# SCH_arduino_uno_cong.net
KiCad netlist of a schematic drawn in Altium Designer
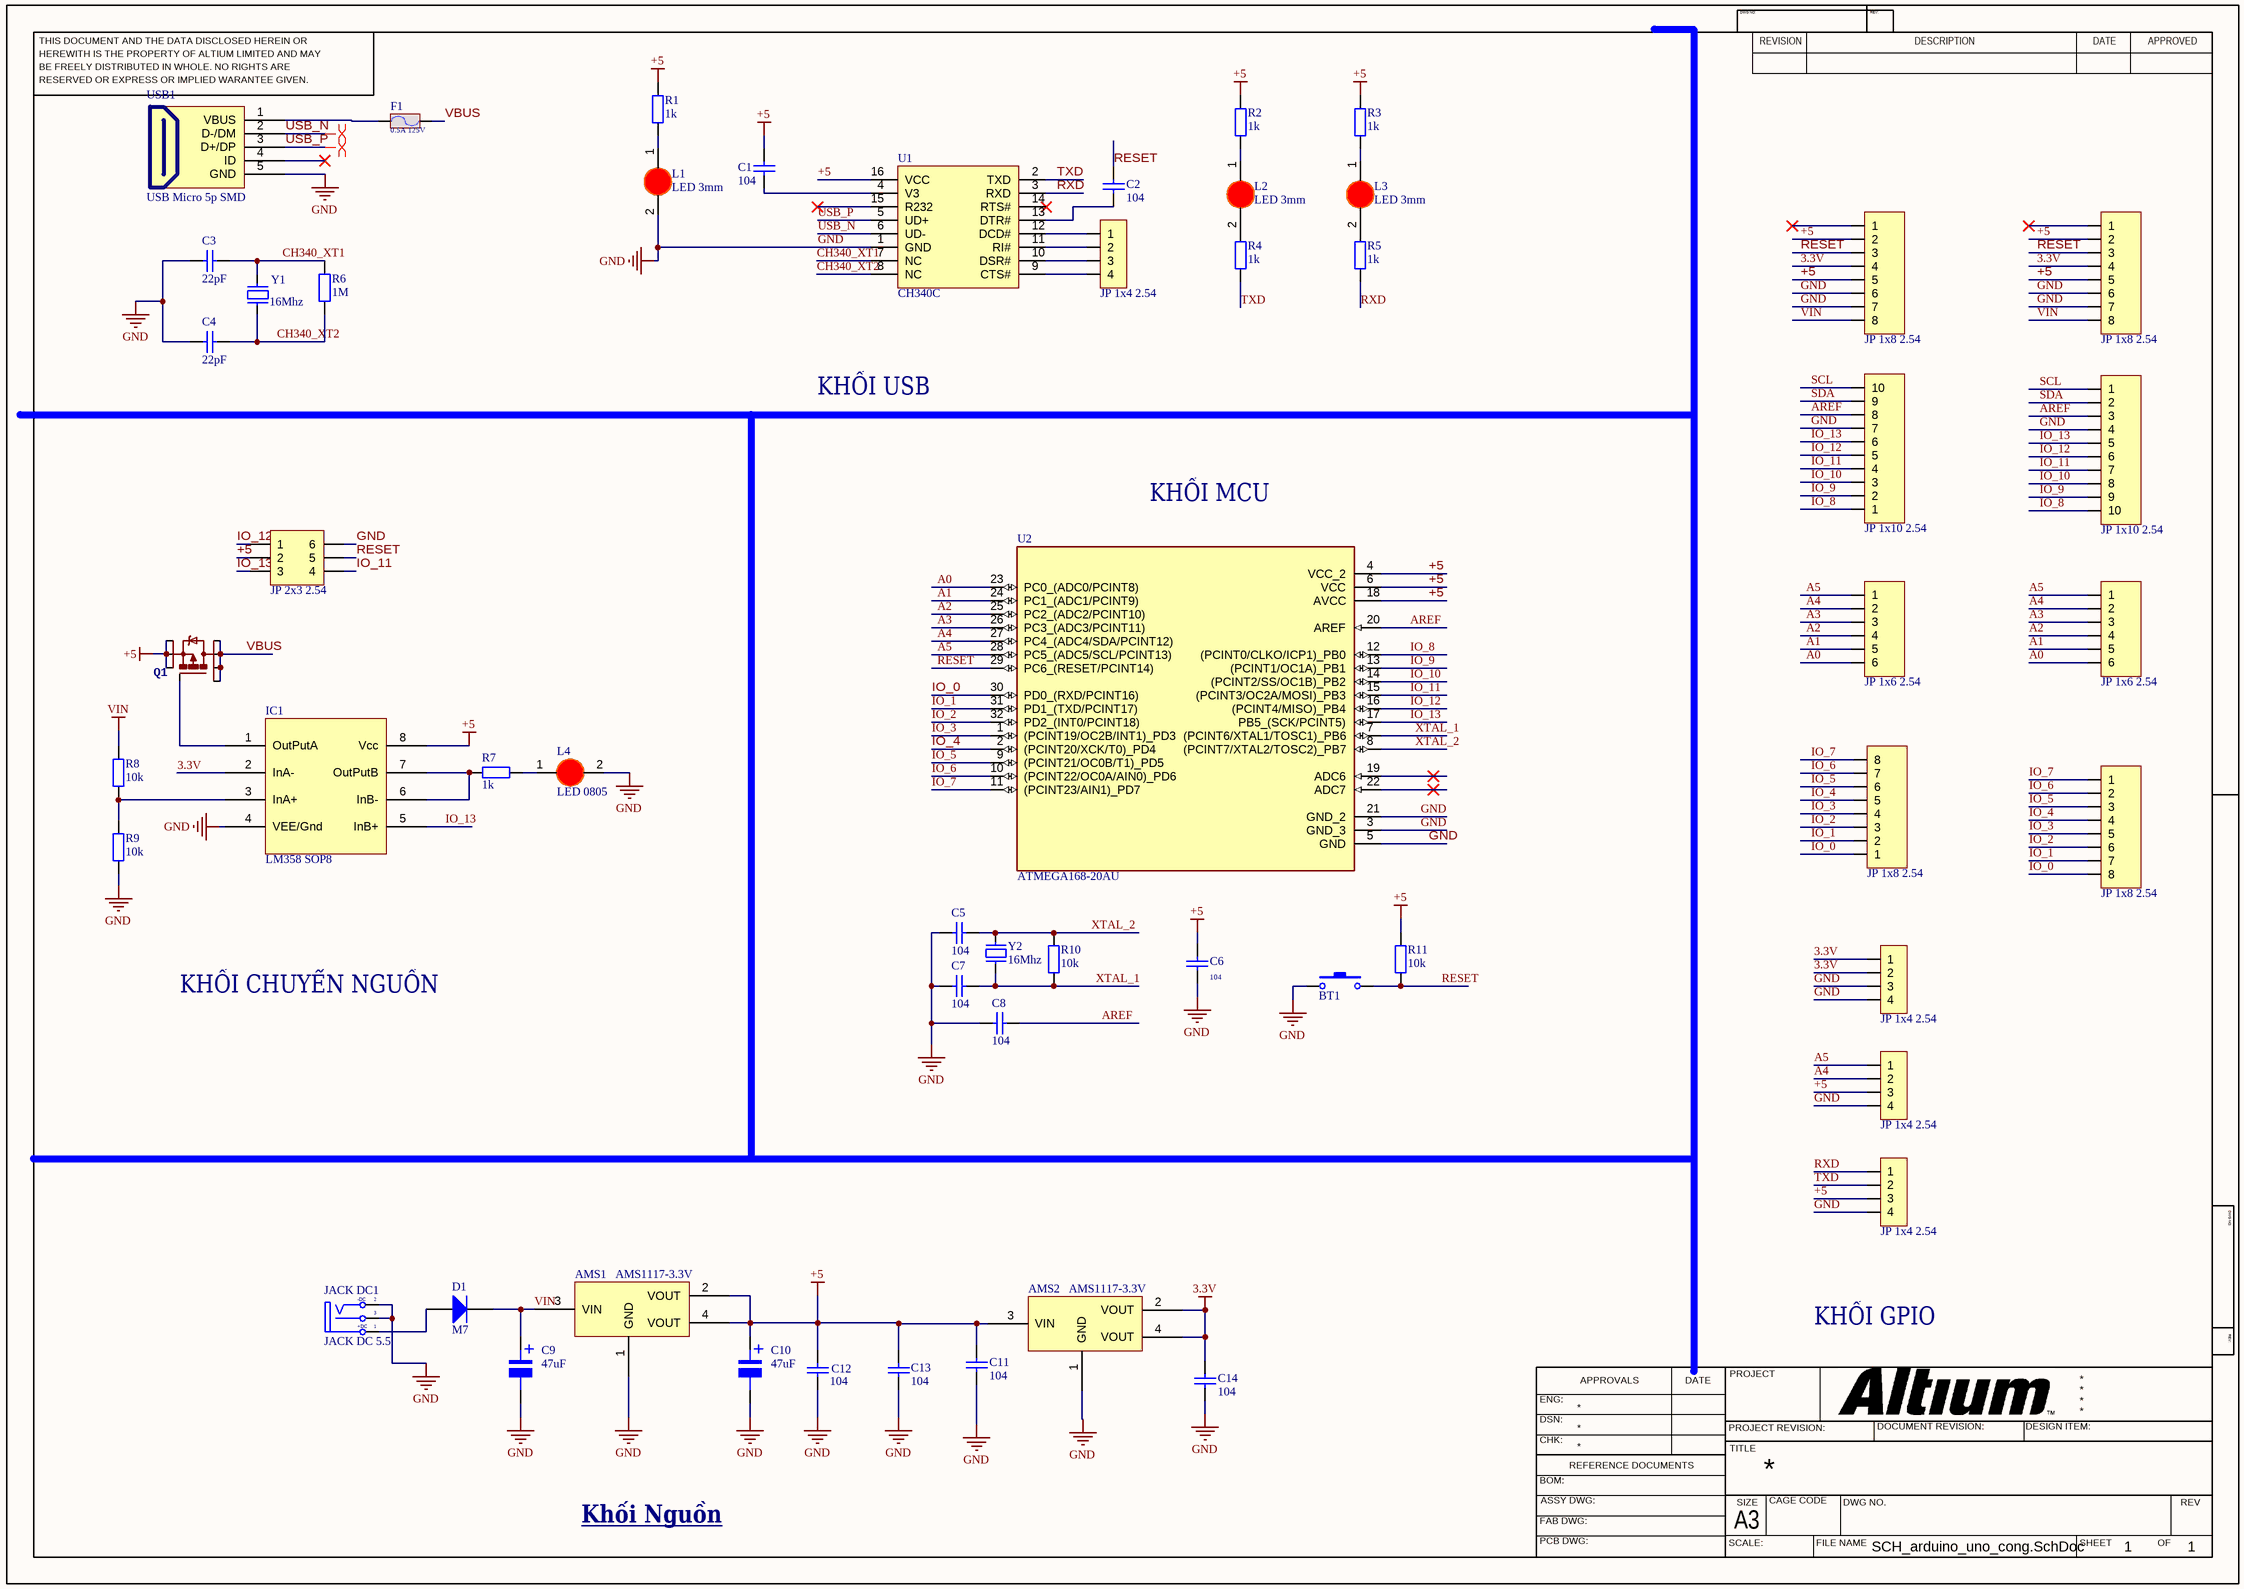
[diagram p0: SCH_arduino_uno_cong.SchDoc]

(export (version "E")
  (design (tool "Eeschema 10.0.6"))
  (components
    (comp (ref "AMS1")
      (value "AMS1117-3.3V")
      (footprint "SOT223")
      (description "Dán")
      (libsource (lib "Altium_Lib_by_KhueNguyenCreator") (part "AMS1117 SMD"))
    )
    (comp (ref "AMS2")
      (value "AMS1117-3.3V")
      (footprint "SOT223")
      (description "Dán")
      (libsource (lib "Altium_Lib_by_KhueNguyenCreator") (part "AMS1117 SMD"))
    )
    (comp (ref "BT1")
      (value "Nut Nhan 2 Chan SMD 3x6x2.5")
      (footprint "Nut Nhan 2 Chan SMD 3x6x2.5")
      (libsource (lib "Altium_Lib_by_KhueNguyenCreator") (part "Nut Nhan 2 Chan SMD 3x6x2.5"))
    )
    (comp (ref "C1")
      (value "104")
      (footprint "tu 0805")
      (description "Dán")
      (libsource (lib "Altium_Lib_by_KhueNguyenCreator") (part "Tu 0805 104 50V 10%"))
    )
    (comp (ref "C2")
      (value "104")
      (footprint "tu 0805")
      (description "Dán")
      (libsource (lib "Altium_Lib_by_KhueNguyenCreator") (part "Tu 0805 104 50V 10%"))
    )
    (comp (ref "C3")
      (value "22pF")
      (footprint "tu 0805")
      (description "Dán")
      (libsource (lib "Altium_Lib_by_KhueNguyenCreator") (part "Tu 0805 22pF 50V 10%"))
    )
    (comp (ref "C4")
      (value "22pF")
      (footprint "tu 0805")
      (description "Dán")
      (libsource (lib "Altium_Lib_by_KhueNguyenCreator") (part "Tu 0805 22pF 50V 10%"))
    )
    (comp (ref "C5")
      (value "104")
      (footprint "tu 0805")
      (description "Dán")
      (libsource (lib "Altium_Lib_by_KhueNguyenCreator") (part "Tu 0805 104 50V 10%"))
    )
    (comp (ref "C6")
      (value "104")
      (footprint "tu 0805")
      (description "Dán")
      (libsource (lib "Altium_Lib_by_KhueNguyenCreator") (part "Tu 0805 104 50V 10%"))
    )
    (comp (ref "C7")
      (value "104")
      (footprint "tu 0805")
      (description "Dán")
      (libsource (lib "Altium_Lib_by_KhueNguyenCreator") (part "Tu 0805 104 50V 10%"))
    )
    (comp (ref "C8")
      (value "104")
      (footprint "tu 0805")
      (description "Dán")
      (libsource (lib "Altium_Lib_by_KhueNguyenCreator") (part "Tu 0805 104 50V 10%"))
    )
    (comp (ref "C9")
      (value "47uF")
      (footprint "tu nhom 6.3 (d)")
      (description "Dán")
      (libsource (lib "Altium_Lib_by_KhueNguyenCreator") (part "Tu Nhom 47uF 25V"))
    )
    (comp (ref "C10")
      (value "47uF")
      (footprint "tu nhom 6.3 (d)")
      (description "Dán")
      (libsource (lib "Altium_Lib_by_KhueNguyenCreator") (part "Tu Nhom 47uF 25V"))
    )
    (comp (ref "C11")
      (value "104")
      (footprint "tu 0805")
      (description "Dán")
      (libsource (lib "Altium_Lib_by_KhueNguyenCreator") (part "Tu 0805 104 50V 10%"))
    )
    (comp (ref "C12")
      (value "104")
      (footprint "tu 0805")
      (description "Dán")
      (libsource (lib "Altium_Lib_by_KhueNguyenCreator") (part "Tu 0805 104 50V 10%"))
    )
    (comp (ref "C13")
      (value "104")
      (footprint "tu 0805")
      (description "Dán")
      (libsource (lib "Altium_Lib_by_KhueNguyenCreator") (part "Tu 0805 104 50V 10%"))
    )
    (comp (ref "C14")
      (value "104")
      (footprint "tu 0805")
      (description "Dán")
      (libsource (lib "Altium_Lib_by_KhueNguyenCreator") (part "Tu 0805 104 50V 10%"))
    )
    (comp (ref "D1")
      (value "M7")
      (footprint "DIODE SMA")
      (description "Dán")
      (libsource (lib "Altium_Lib_by_KhueNguyenCreator") (part "Diode M7 ( 4007 )"))
    )
    (comp (ref "F1")
      (value "0.5A 125V")
      (footprint "Cau Chi SMD1808")
      (description "Cau chi 0.5A 125V SMD1808")
      (libsource (lib "Altium_Lib_by_KhueNguyenCreator") (part "Cau chi 0.5A 125V SMD1808"))
    )
    (comp (ref "IC1")
      (value "LM358 SOP8")
      (footprint "SOP 8")
      (description "Dán")
      (libsource (lib "Altium_Lib_by_KhueNguyenCreator") (part "LM358 SOP8"))
    )
    (comp (ref "JACK DC1")
      (value "JACK DC 5.5")
      (footprint "JACK DC 5.5")
      (libsource (lib "Altium_Lib_by_KhueNguyenCreator") (part "JACK DC 5.5"))
    )
    (comp (ref "JP1")
      (value "JP 1x8 2.54")
      (footprint "JP 1x8 CT")
      (description "Cắm")
      (libsource (lib "Altium_Lib_by_KhueNguyenCreator") (part "JP 1x8 2.54 Cai Thang"))
    )
    (comp (ref "JP2")
      (value "JP 1x8 2.54")
      (footprint "JP 1x8 DT")
      (description "Cắm")
      (libsource (lib "Altium_Lib_by_KhueNguyenCreator") (part "JP 1x8 2.54 Duc Thang"))
    )
    (comp (ref "JP3")
      (value "JP 1x4 2.54")
      (footprint "JP 1x4 CT")
      (description "Cắm")
      (libsource (lib "Altium_Lib_by_KhueNguyenCreator") (part "JP 1x4 2.54 Cai Thang"))
    )
    (comp (ref "JP4")
      (value "JP 1x10 2.54")
      (footprint "JP 1x10 CT")
      (description "Cắm")
      (libsource (lib "Altium_Lib_by_KhueNguyenCreator") (part "JP 1x10 2.54 Cai Thang"))
    )
    (comp (ref "JP5")
      (value "JP 1x10 2.54")
      (footprint "JP 1x10 DT")
      (description "Cắm")
      (libsource (lib "Altium_Lib_by_KhueNguyenCreator") (part "JP 1x10 2.54 Duc Thang"))
    )
    (comp (ref "JP6")
      (value "JP 2x3 2.54")
      (footprint "JP 2x3 DT")
      (description "Cắm")
      (libsource (lib "Altium_Lib_by_KhueNguyenCreator") (part "JP 2x3 2.54 Duc Thang"))
    )
    (comp (ref "JP7")
      (value "JP 1x6 2.54")
      (footprint "JP 1x6 CT")
      (description "Cắm")
      (libsource (lib "Altium_Lib_by_KhueNguyenCreator") (part "JP 1x6 2.54 Cai Thang"))
    )
    (comp (ref "JP8")
      (value "JP 1x6 2.54")
      (footprint "JP 1x6 DT")
      (description "Cắm")
      (libsource (lib "Altium_Lib_by_KhueNguyenCreator") (part "JP 1x6 2.54 Duc Thang"))
    )
    (comp (ref "JP9")
      (value "JP 1x8 2.54")
      (footprint "JP 1x8 CT")
      (description "Cắm")
      (libsource (lib "") (part "JP 1x8 2.54 Cai Thang_1"))
    )
    (comp (ref "JP10")
      (value "JP 1x8 2.54")
      (footprint "JP 1x8 DT")
      (description "Cắm")
      (libsource (lib "Altium_Lib_by_KhueNguyenCreator") (part "JP 1x8 2.54 Duc Thang"))
    )
    (comp (ref "JP11")
      (value "JP 1x4 2.54")
      (footprint "JP 1x4 CT")
      (description "Cắm")
      (libsource (lib "Altium_Lib_by_KhueNguyenCreator") (part "JP 1x4 2.54 Cai Thang"))
    )
    (comp (ref "JP12")
      (value "JP 1x4 2.54")
      (footprint "JP 1x4 CT")
      (description "Cắm")
      (libsource (lib "Altium_Lib_by_KhueNguyenCreator") (part "JP 1x4 2.54 Cai Thang"))
    )
    (comp (ref "JP13")
      (value "JP 1x4 2.54")
      (footprint "JP 1x4 CT")
      (description "Cắm")
      (libsource (lib "Altium_Lib_by_KhueNguyenCreator") (part "JP 1x4 2.54 Cai Thang"))
    )
    (comp (ref "L1")
      (value "LED 3mm")
      (footprint "LED-3MM-RED")
      (description "Cắm")
      (libsource (lib "Altium_Lib_by_KhueNguyenCreator") (part "LED 3mm Do"))
    )
    (comp (ref "L2")
      (value "LED 3mm")
      (footprint "LED-3MM-RED")
      (description "Cắm")
      (libsource (lib "Altium_Lib_by_KhueNguyenCreator") (part "LED 3mm Do"))
    )
    (comp (ref "L3")
      (value "LED 3mm")
      (footprint "LED-3MM-RED")
      (description "Cắm")
      (libsource (lib "Altium_Lib_by_KhueNguyenCreator") (part "LED 3mm Do"))
    )
    (comp (ref "L4")
      (value "LED 0805")
      (footprint "LED-0805-Red")
      (description "Dán")
      (libsource (lib "Altium_Lib_by_KhueNguyenCreator") (part "LED 0805 Do"))
    )
    (comp (ref "Q1")
      (value "MOSFET_P")
      (footprint "SO-8")
      (description "MOSFET P-CH 30V 5.8A 8-SOIC")
      (fields (field (name "PART NUMBER") "Q000008") (field (name "MANUFACTURER PART NUMBER") "IRF7406TRPBF"))
      (libsource (lib "open-components") (part "MOSFET_P"))
    )
    (comp (ref "R1")
      (value "1k")
      (footprint "tro smd 0805")
      (description "Dán")
      (libsource (lib "Altium_Lib_by_KhueNguyenCreator") (part "Tro 0805 1% 1k"))
    )
    (comp (ref "R2")
      (value "1k")
      (footprint "tro smd 0805")
      (description "Dán")
      (libsource (lib "Altium_Lib_by_KhueNguyenCreator") (part "Tro 0805 1% 1k"))
    )
    (comp (ref "R3")
      (value "1k")
      (footprint "tro smd 0805")
      (description "Dán")
      (libsource (lib "Altium_Lib_by_KhueNguyenCreator") (part "Tro 0805 1% 1k"))
    )
    (comp (ref "R4")
      (value "1k")
      (footprint "tro smd 0805")
      (description "Dán")
      (libsource (lib "Altium_Lib_by_KhueNguyenCreator") (part "Tro 0805 1% 1k"))
    )
    (comp (ref "R5")
      (value "1k")
      (footprint "tro smd 0805")
      (description "Dán")
      (libsource (lib "Altium_Lib_by_KhueNguyenCreator") (part "Tro 0805 1% 1k"))
    )
    (comp (ref "R6")
      (value "1M")
      (footprint "tro smd 0805")
      (description "Dán")
      (libsource (lib "Altium_Lib_by_KhueNguyenCreator") (part "Tro 0805 5% 1M"))
    )
    (comp (ref "R7")
      (value "1k")
      (footprint "tro smd 0805")
      (description "Dán")
      (libsource (lib "Altium_Lib_by_KhueNguyenCreator") (part "Tro 0805 5% 1k"))
    )
    (comp (ref "R8")
      (value "10k")
      (footprint "tro smd 0805")
      (description "Dán")
      (libsource (lib "Altium_Lib_by_KhueNguyenCreator") (part "Tro 0805 1% 10k"))
    )
    (comp (ref "R9")
      (value "10k")
      (footprint "tro smd 0805")
      (description "Dán")
      (libsource (lib "Altium_Lib_by_KhueNguyenCreator") (part "Tro 0805 1% 10k"))
    )
    (comp (ref "R10")
      (value "10k")
      (footprint "tro smd 0805")
      (description "Dán")
      (libsource (lib "Altium_Lib_by_KhueNguyenCreator") (part "Tro 0805 1% 10k"))
    )
    (comp (ref "R11")
      (value "10k")
      (footprint "tro smd 0805")
      (description "Dán")
      (libsource (lib "Altium_Lib_by_KhueNguyenCreator") (part "Tro 0805 5% 10k"))
    )
    (comp (ref "U1")
      (value "CH340C")
      (footprint "SOIC16_50_284_25X90_SMT")
      (description "USB Bridge, USB to UART USB 2.0 UART Interface")
      (fields (field (name "MANUFACTURER") "Olimex"))
      (libsource (lib "Altium_Lib_by_KhueNguyenCreator") (part "CH340C"))
    )
    (comp (ref "U2")
      (value "ATMEGA168-20AU")
      (footprint "ATMEGA168")
      (description "AVR AVRÂ® ATmega Microcontroller IC 8-Bit 20MHz 16KB _8K x 16_ FLASH 32-TQFP _7x7_")
      (fields (field (name "MF") "Microchip"))
      (libsource (lib "Altium_Lib_by_KhueNguyenCreator") (part "ATMEGA168-20AU"))
    )
    (comp (ref "USB1")
      (value "USB Micro 5p SMD")
      (footprint "USB Micro 5p SMD")
      (description "USB Type B")
      (libsource (lib "Altium_Lib_by_KhueNguyenCreator") (part "USB Micro 5p SMD"))
    )
    (comp (ref "Y1")
      (value "16Mhz")
      (footprint "Thach Anh 2 chan SMD")
      (description "Crystal For all Crystal 2pin.")
      (libsource (lib "Altium_Lib_by_KhueNguyenCreator") (part "Thach Anh 2 chan SMD"))
    )
    (comp (ref "Y2")
      (value "16Mhz")
      (footprint "Thach Anh 2 chan SMD")
      (description "Crystal For all Crystal 2pin.")
      (libsource (lib "Altium_Lib_by_KhueNguyenCreator") (part "Thach Anh 2 chan SMD"))
    )
  )
  (nets
    (net (code "1") (name "+5") (class "Default")
      (node (ref "AMS1") (pin "2") (pinfunction "VOUT_2") (pintype "passive"))
      (node (ref "AMS1") (pin "4") (pinfunction "VOUT_4") (pintype "passive"))
      (node (ref "AMS2") (pin "3") (pinfunction "VIN_3") (pintype "passive"))
      (node (ref "C1") (pin "1") (pinfunction "1_1") (pintype "passive"))
      (node (ref "C10") (pin "1") (pinfunction "1_1") (pintype "passive"))
      (node (ref "C11") (pin "2") (pinfunction "2_2") (pintype "passive"))
      (node (ref "C12") (pin "2") (pinfunction "2_2") (pintype "passive"))
      (node (ref "C13") (pin "2") (pinfunction "2_2") (pintype "passive"))
      (node (ref "C6") (pin "1") (pinfunction "1_1") (pintype "passive"))
      (node (ref "IC1") (pin "8") (pinfunction "Vcc_8") (pintype "passive"))
      (node (ref "JP1") (pin "2") (pinfunction "2_2") (pintype "passive"))
      (node (ref "JP1") (pin "5") (pinfunction "5_5") (pintype "passive"))
      (node (ref "JP12") (pin "3") (pinfunction "3_3") (pintype "passive"))
      (node (ref "JP13") (pin "3") (pinfunction "3_3") (pintype "passive"))
      (node (ref "JP2") (pin "2") (pinfunction "2_2") (pintype "passive"))
      (node (ref "JP2") (pin "5") (pinfunction "5_5") (pintype "passive"))
      (node (ref "JP6") (pin "2") (pinfunction "2_2") (pintype "passive"))
      (node (ref "Q1") (pin "1") (pinfunction "S_1") (pintype "passive"))
      (node (ref "Q1") (pin "2") (pinfunction "S_2") (pintype "passive"))
      (node (ref "Q1") (pin "3") (pinfunction "S_3") (pintype "passive"))
      (node (ref "R1") (pin "2") (pinfunction "2_2") (pintype "passive"))
      (node (ref "R11") (pin "2") (pinfunction "2_2") (pintype "passive"))
      (node (ref "R2") (pin "2") (pinfunction "2_2") (pintype "passive"))
      (node (ref "R3") (pin "2") (pinfunction "2_2") (pintype "passive"))
      (node (ref "U1") (pin "16") (pinfunction "VCC_16") (pintype "passive"))
      (node (ref "U2") (pin "18") (pinfunction "AVCC_18") (pintype "power_in"))
      (node (ref "U2") (pin "4") (pinfunction "VCC_2_4") (pintype "power_in"))
      (node (ref "U2") (pin "6") (pinfunction "VCC_6") (pintype "power_in"))
    )
    (net (code "2") (name "/A0") (class "Default")
      (node (ref "JP7") (pin "6") (pinfunction "6_6") (pintype "passive"))
      (node (ref "JP8") (pin "6") (pinfunction "6_6") (pintype "passive"))
      (node (ref "U2") (pin "23") (pinfunction "PC0_(ADC0/PCINT8)_23") (pintype "bidirectional"))
    )
    (net (code "3") (name "/A1") (class "Default")
      (node (ref "JP7") (pin "5") (pinfunction "5_5") (pintype "passive"))
      (node (ref "JP8") (pin "5") (pinfunction "5_5") (pintype "passive"))
      (node (ref "U2") (pin "24") (pinfunction "PC1_(ADC1/PCINT9)_24") (pintype "bidirectional"))
    )
    (net (code "4") (name "/A2") (class "Default")
      (node (ref "JP7") (pin "4") (pinfunction "4_4") (pintype "passive"))
      (node (ref "JP8") (pin "4") (pinfunction "4_4") (pintype "passive"))
      (node (ref "U2") (pin "25") (pinfunction "PC2_(ADC2/PCINT10)_25") (pintype "bidirectional"))
    )
    (net (code "5") (name "/A3") (class "Default")
      (node (ref "JP7") (pin "3") (pinfunction "3_3") (pintype "passive"))
      (node (ref "JP8") (pin "3") (pinfunction "3_3") (pintype "passive"))
      (node (ref "U2") (pin "26") (pinfunction "PC3_(ADC3/PCINT11)_26") (pintype "bidirectional"))
    )
    (net (code "6") (name "/A4") (class "Default")
      (node (ref "JP12") (pin "2") (pinfunction "2_2") (pintype "passive"))
      (node (ref "JP7") (pin "2") (pinfunction "2_2") (pintype "passive"))
      (node (ref "JP8") (pin "2") (pinfunction "2_2") (pintype "passive"))
      (node (ref "U2") (pin "27") (pinfunction "PC4_(ADC4/SDA/PCINT12)_27") (pintype "bidirectional"))
    )
    (net (code "7") (name "/A5") (class "Default")
      (node (ref "JP12") (pin "1") (pinfunction "1_1") (pintype "passive"))
      (node (ref "JP7") (pin "1") (pinfunction "1_1") (pintype "passive"))
      (node (ref "JP8") (pin "1") (pinfunction "1_1") (pintype "passive"))
      (node (ref "U2") (pin "28") (pinfunction "PC5_(ADC5/SCL/PCINT13)_28") (pintype "bidirectional"))
    )
    (net (code "8") (name "/AREF") (class "Default")
      (node (ref "C8") (pin "1") (pinfunction "1_1") (pintype "passive"))
      (node (ref "JP4") (pin "8") (pinfunction "8_8") (pintype "passive"))
      (node (ref "JP5") (pin "3") (pinfunction "3_3") (pintype "passive"))
      (node (ref "U2") (pin "20") (pinfunction "AREF_20") (pintype "input"))
    )
    (net (code "9") (name "/CH340_XT1") (class "Default")
      (node (ref "C3") (pin "1") (pinfunction "1_1") (pintype "passive"))
      (node (ref "R6") (pin "2") (pinfunction "2_2") (pintype "passive"))
      (node (ref "U1") (pin "7") (pinfunction "NC_7") (pintype "passive"))
      (node (ref "Y1") (pin "2") (pinfunction "2_2") (pintype "passive"))
    )
    (net (code "10") (name "/CH340_XT2") (class "Default")
      (node (ref "C4") (pin "1") (pinfunction "1_1") (pintype "passive"))
      (node (ref "R6") (pin "1") (pinfunction "1_1") (pintype "passive"))
      (node (ref "U1") (pin "8") (pinfunction "NC_8") (pintype "passive"))
      (node (ref "Y1") (pin "1") (pinfunction "1_1") (pintype "passive"))
    )
    (net (code "11") (name "/IO_0") (class "Default")
      (node (ref "JP10") (pin "8") (pinfunction "8_8") (pintype "passive"))
      (node (ref "JP9") (pin "1") (pinfunction "1_1") (pintype "passive"))
      (node (ref "U2") (pin "30") (pinfunction "PD0_(RXD/PCINT16)_30") (pintype "bidirectional"))
    )
    (net (code "12") (name "/IO_1") (class "Default")
      (node (ref "JP10") (pin "7") (pinfunction "7_7") (pintype "passive"))
      (node (ref "JP9") (pin "2") (pinfunction "2_2") (pintype "passive"))
      (node (ref "U2") (pin "31") (pinfunction "PD1_(TXD/PCINT17)_31") (pintype "bidirectional"))
    )
    (net (code "13") (name "/IO_2") (class "Default")
      (node (ref "JP10") (pin "6") (pinfunction "6_6") (pintype "passive"))
      (node (ref "JP9") (pin "3") (pinfunction "3_3") (pintype "passive"))
      (node (ref "U2") (pin "32") (pinfunction "PD2_(INT0/PCINT18)_32") (pintype "bidirectional"))
    )
    (net (code "14") (name "/IO_3") (class "Default")
      (node (ref "JP10") (pin "5") (pinfunction "5_5") (pintype "passive"))
      (node (ref "JP9") (pin "4") (pinfunction "4_4") (pintype "passive"))
      (node (ref "U2") (pin "1") (pinfunction "(PCINT19/OC2B/INT1)_PD3_1") (pintype "bidirectional"))
    )
    (net (code "15") (name "/IO_4") (class "Default")
      (node (ref "JP10") (pin "4") (pinfunction "4_4") (pintype "passive"))
      (node (ref "JP9") (pin "5") (pinfunction "5_5") (pintype "passive"))
      (node (ref "U2") (pin "2") (pinfunction "(PCINT20/XCK/T0)_PD4_2") (pintype "bidirectional"))
    )
    (net (code "16") (name "/IO_5") (class "Default")
      (node (ref "JP10") (pin "3") (pinfunction "3_3") (pintype "passive"))
      (node (ref "JP9") (pin "6") (pinfunction "6_6") (pintype "passive"))
      (node (ref "U2") (pin "9") (pinfunction "(PCINT21/OC0B/T1)_PD5_9") (pintype "bidirectional"))
    )
    (net (code "17") (name "/IO_6") (class "Default")
      (node (ref "JP10") (pin "2") (pinfunction "2_2") (pintype "passive"))
      (node (ref "JP9") (pin "7") (pinfunction "7_7") (pintype "passive"))
      (node (ref "U2") (pin "10") (pinfunction "(PCINT22/OC0A/AIN0)_PD6_10") (pintype "bidirectional"))
    )
    (net (code "18") (name "/IO_7") (class "Default")
      (node (ref "JP10") (pin "1") (pinfunction "1_1") (pintype "passive"))
      (node (ref "JP9") (pin "8") (pinfunction "8_8") (pintype "passive"))
      (node (ref "U2") (pin "11") (pinfunction "(PCINT23/AIN1)_PD7_11") (pintype "bidirectional"))
    )
    (net (code "19") (name "/IO_8") (class "Default")
      (node (ref "JP4") (pin "1") (pinfunction "1_1") (pintype "passive"))
      (node (ref "JP5") (pin "10") (pinfunction "10_10") (pintype "passive"))
      (node (ref "U2") (pin "12") (pinfunction "(PCINT0/CLKO/ICP1)_PB0_12") (pintype "bidirectional"))
    )
    (net (code "20") (name "/IO_9") (class "Default")
      (node (ref "JP4") (pin "2") (pinfunction "2_2") (pintype "passive"))
      (node (ref "JP5") (pin "9") (pinfunction "9_9") (pintype "passive"))
      (node (ref "U2") (pin "13") (pinfunction "(PCINT1/OC1A)_PB1_13") (pintype "bidirectional"))
    )
    (net (code "21") (name "/IO_10") (class "Default")
      (node (ref "JP4") (pin "3") (pinfunction "3_3") (pintype "passive"))
      (node (ref "JP5") (pin "8") (pinfunction "8_8") (pintype "passive"))
      (node (ref "U2") (pin "14") (pinfunction "(PCINT2/SS/OC1B)_PB2_14") (pintype "bidirectional"))
    )
    (net (code "22") (name "/IO_11") (class "Default")
      (node (ref "JP4") (pin "4") (pinfunction "4_4") (pintype "passive"))
      (node (ref "JP5") (pin "7") (pinfunction "7_7") (pintype "passive"))
      (node (ref "JP6") (pin "4") (pinfunction "4_4") (pintype "passive"))
      (node (ref "U2") (pin "15") (pinfunction "(PCINT3/OC2A/MOSI)_PB3_15") (pintype "bidirectional"))
    )
    (net (code "23") (name "/IO_12") (class "Default")
      (node (ref "JP4") (pin "5") (pinfunction "5_5") (pintype "passive"))
      (node (ref "JP5") (pin "6") (pinfunction "6_6") (pintype "passive"))
      (node (ref "JP6") (pin "1") (pinfunction "1_1") (pintype "passive"))
      (node (ref "U2") (pin "16") (pinfunction "(PCINT4/MISO)_PB4_16") (pintype "bidirectional"))
    )
    (net (code "24") (name "/IO_13") (class "Default")
      (node (ref "IC1") (pin "5") (pinfunction "InB+_5") (pintype "passive"))
      (node (ref "JP4") (pin "6") (pinfunction "6_6") (pintype "passive"))
      (node (ref "JP5") (pin "5") (pinfunction "5_5") (pintype "passive"))
      (node (ref "JP6") (pin "3") (pinfunction "3_3") (pintype "passive"))
      (node (ref "U2") (pin "17") (pinfunction "PB5_(SCK/PCINT5)_17") (pintype "bidirectional"))
    )
    (net (code "25") (name "/RESET") (class "Default")
      (node (ref "BT1") (pin "2") (pinfunction "2_2") (pintype "passive"))
      (node (ref "C2") (pin "1") (pinfunction "1_1") (pintype "passive"))
      (node (ref "JP1") (pin "3") (pinfunction "3_3") (pintype "passive"))
      (node (ref "JP2") (pin "3") (pinfunction "3_3") (pintype "passive"))
      (node (ref "JP6") (pin "5") (pinfunction "5_5") (pintype "passive"))
      (node (ref "R11") (pin "1") (pinfunction "1_1") (pintype "passive"))
      (node (ref "U2") (pin "29") (pinfunction "PC6_(RESET/PCINT14)_29") (pintype "bidirectional"))
    )
    (net (code "26") (name "/RXD") (class "Default")
      (node (ref "JP13") (pin "1") (pinfunction "1_1") (pintype "passive"))
      (node (ref "R5") (pin "1") (pinfunction "1_1") (pintype "passive"))
      (node (ref "U1") (pin "3") (pinfunction "RXD_3") (pintype "passive"))
    )
    (net (code "27") (name "/SCL") (class "Default")
      (node (ref "JP4") (pin "10") (pinfunction "10_10") (pintype "passive"))
      (node (ref "JP5") (pin "1") (pinfunction "1_1") (pintype "passive"))
    )
    (net (code "28") (name "/SDA") (class "Default")
      (node (ref "JP4") (pin "9") (pinfunction "9_9") (pintype "passive"))
      (node (ref "JP5") (pin "2") (pinfunction "2_2") (pintype "passive"))
    )
    (net (code "29") (name "/TXD") (class "Default")
      (node (ref "JP13") (pin "2") (pinfunction "2_2") (pintype "passive"))
      (node (ref "R4") (pin "1") (pinfunction "1_1") (pintype "passive"))
      (node (ref "U1") (pin "2") (pinfunction "TXD_2") (pintype "passive"))
    )
    (net (code "30") (name "/USB_N") (class "Default")
      (node (ref "U1") (pin "6") (pinfunction "UD-_6") (pintype "passive"))
      (node (ref "USB1") (pin "2") (pinfunction "D-/DM_2") (pintype "passive"))
    )
    (net (code "31") (name "/USB_P") (class "Default")
      (node (ref "U1") (pin "5") (pinfunction "UD+_5") (pintype "passive"))
      (node (ref "USB1") (pin "3") (pinfunction "D+/DP_3") (pintype "passive"))
    )
    (net (code "32") (name "/VBUS") (class "Default")
      (node (ref "F1") (pin "2") (pinfunction "2_2") (pintype "passive"))
      (node (ref "Q1") (pin "5") (pinfunction "D_5") (pintype "passive"))
      (node (ref "Q1") (pin "6") (pinfunction "D_6") (pintype "passive"))
      (node (ref "Q1") (pin "7") (pinfunction "D_7") (pintype "passive"))
      (node (ref "Q1") (pin "8") (pinfunction "D_8") (pintype "passive"))
    )
    (net (code "33") (name "/XTAL_1") (class "Default")
      (node (ref "C7") (pin "1") (pinfunction "1_1") (pintype "passive"))
      (node (ref "R10") (pin "1") (pinfunction "1_1") (pintype "passive"))
      (node (ref "U2") (pin "7") (pinfunction "(PCINT6/XTAL1/TOSC1)_PB6_7") (pintype "bidirectional"))
      (node (ref "Y2") (pin "1") (pinfunction "1_1") (pintype "passive"))
    )
    (net (code "34") (name "/XTAL_2") (class "Default")
      (node (ref "C5") (pin "1") (pinfunction "1_1") (pintype "passive"))
      (node (ref "R10") (pin "2") (pinfunction "2_2") (pintype "passive"))
      (node (ref "U2") (pin "8") (pinfunction "(PCINT7/XTAL2/TOSC2)_PB7_8") (pintype "bidirectional"))
      (node (ref "Y2") (pin "2") (pinfunction "2_2") (pintype "passive"))
    )
    (net (code "35") (name "3.3V") (class "Default")
      (node (ref "AMS2") (pin "2") (pinfunction "VOUT_2") (pintype "passive"))
      (node (ref "AMS2") (pin "4") (pinfunction "VOUT_4") (pintype "passive"))
      (node (ref "C14") (pin "2") (pinfunction "2_2") (pintype "passive"))
      (node (ref "IC1") (pin "2") (pinfunction "InA-_2") (pintype "passive"))
      (node (ref "JP1") (pin "4") (pinfunction "4_4") (pintype "passive"))
      (node (ref "JP11") (pin "1") (pinfunction "1_1") (pintype "passive"))
      (node (ref "JP11") (pin "2") (pinfunction "2_2") (pintype "passive"))
      (node (ref "JP2") (pin "4") (pinfunction "4_4") (pintype "passive"))
    )
    (net (code "36") (name "GND") (class "Default")
      (node (ref "AMS1") (pin "1") (pinfunction "GND_1") (pintype "passive"))
      (node (ref "AMS2") (pin "1") (pinfunction "GND_1") (pintype "passive"))
      (node (ref "BT1") (pin "1") (pinfunction "1_1") (pintype "passive"))
      (node (ref "C10") (pin "2") (pinfunction "2_2") (pintype "passive"))
      (node (ref "C11") (pin "1") (pinfunction "1_1") (pintype "passive"))
      (node (ref "C12") (pin "1") (pinfunction "1_1") (pintype "passive"))
      (node (ref "C13") (pin "1") (pinfunction "1_1") (pintype "passive"))
      (node (ref "C14") (pin "1") (pinfunction "1_1") (pintype "passive"))
      (node (ref "C3") (pin "2") (pinfunction "2_2") (pintype "passive"))
      (node (ref "C4") (pin "2") (pinfunction "2_2") (pintype "passive"))
      (node (ref "C5") (pin "2") (pinfunction "2_2") (pintype "passive"))
      (node (ref "C6") (pin "2") (pinfunction "2_2") (pintype "passive"))
      (node (ref "C7") (pin "2") (pinfunction "2_2") (pintype "passive"))
      (node (ref "C8") (pin "2") (pinfunction "2_2") (pintype "passive"))
      (node (ref "C9") (pin "2") (pinfunction "2_2") (pintype "passive"))
      (node (ref "IC1") (pin "4") (pinfunction "VEE/Gnd_4") (pintype "passive"))
      (node (ref "JACK DC1") (pin "2") (pinfunction "TN_2") (pintype "passive"))
      (node (ref "JACK DC1") (pin "3") (pinfunction "S_3") (pintype "power_in"))
      (node (ref "JP1") (pin "6") (pinfunction "6_6") (pintype "passive"))
      (node (ref "JP1") (pin "7") (pinfunction "7_7") (pintype "passive"))
      (node (ref "JP11") (pin "3") (pinfunction "3_3") (pintype "passive"))
      (node (ref "JP11") (pin "4") (pinfunction "4_4") (pintype "passive"))
      (node (ref "JP12") (pin "4") (pinfunction "4_4") (pintype "passive"))
      (node (ref "JP13") (pin "4") (pinfunction "4_4") (pintype "passive"))
      (node (ref "JP2") (pin "6") (pinfunction "6_6") (pintype "passive"))
      (node (ref "JP2") (pin "7") (pinfunction "7_7") (pintype "passive"))
      (node (ref "JP4") (pin "7") (pinfunction "7_7") (pintype "passive"))
      (node (ref "JP5") (pin "4") (pinfunction "4_4") (pintype "passive"))
      (node (ref "JP6") (pin "6") (pinfunction "6_6") (pintype "passive"))
      (node (ref "L1") (pin "2") (pinfunction "K_2") (pintype "passive"))
      (node (ref "L4") (pin "2") (pinfunction "K_2") (pintype "passive"))
      (node (ref "R9") (pin "1") (pinfunction "1_1") (pintype "passive"))
      (node (ref "U1") (pin "1") (pinfunction "GND_1") (pintype "passive"))
      (node (ref "U2") (pin "21") (pinfunction "GND_2_21") (pintype "passive"))
      (node (ref "U2") (pin "3") (pinfunction "GND_3_3") (pintype "passive"))
      (node (ref "U2") (pin "5") (pinfunction "GND_5") (pintype "passive"))
      (node (ref "USB1") (pin "5") (pinfunction "GND_5") (pintype "passive"))
    )
    (net (code "37") (name "Net-(D1-A)") (class "Default")
      (node (ref "D1") (pin "1") (pinfunction "A_1") (pintype "passive"))
      (node (ref "JACK DC1") (pin "1") (pinfunction "T_1") (pintype "passive"))
    )
    (net (code "38") (name "Net-(IC1-InA+)") (class "Default")
      (node (ref "IC1") (pin "3") (pinfunction "InA+_3") (pintype "passive"))
      (node (ref "R8") (pin "1") (pinfunction "1_1") (pintype "passive"))
      (node (ref "R9") (pin "2") (pinfunction "2_2") (pintype "passive"))
    )
    (net (code "39") (name "Net-(IC1-InB-)") (class "Default")
      (node (ref "IC1") (pin "6") (pinfunction "InB-_6") (pintype "passive"))
      (node (ref "IC1") (pin "7") (pinfunction "OutPutB_7") (pintype "passive"))
      (node (ref "R7") (pin "1") (pinfunction "1_1") (pintype "passive"))
    )
    (net (code "40") (name "Net-(IC1-OutPutA)") (class "Default")
      (node (ref "IC1") (pin "1") (pinfunction "OutPutA_1") (pintype "passive"))
      (node (ref "Q1") (pin "4") (pinfunction "G_4") (pintype "passive"))
    )
    (net (code "41") (name "Net-(L1-A)") (class "Default")
      (node (ref "L1") (pin "1") (pinfunction "A_1") (pintype "passive"))
      (node (ref "R1") (pin "1") (pinfunction "1_1") (pintype "passive"))
    )
    (net (code "42") (name "Net-(L2-A)") (class "Default")
      (node (ref "L2") (pin "1") (pinfunction "A_1") (pintype "passive"))
      (node (ref "R2") (pin "1") (pinfunction "1_1") (pintype "passive"))
    )
    (net (code "43") (name "Net-(L2-K)") (class "Default")
      (node (ref "L2") (pin "2") (pinfunction "K_2") (pintype "passive"))
      (node (ref "R4") (pin "2") (pinfunction "2_2") (pintype "passive"))
    )
    (net (code "44") (name "Net-(L3-A)") (class "Default")
      (node (ref "L3") (pin "1") (pinfunction "A_1") (pintype "passive"))
      (node (ref "R3") (pin "1") (pinfunction "1_1") (pintype "passive"))
    )
    (net (code "45") (name "Net-(L3-K)") (class "Default")
      (node (ref "L3") (pin "2") (pinfunction "K_2") (pintype "passive"))
      (node (ref "R5") (pin "2") (pinfunction "2_2") (pintype "passive"))
    )
    (net (code "46") (name "Net-(L4-A)") (class "Default")
      (node (ref "L4") (pin "1") (pinfunction "A_1") (pintype "passive"))
      (node (ref "R7") (pin "2") (pinfunction "2_2") (pintype "passive"))
    )
    (net (code "47") (name "Net-(U1-CTS#)") (class "Default")
      (node (ref "JP3") (pin "4") (pinfunction "4_4") (pintype "passive"))
      (node (ref "U1") (pin "9") (pinfunction "CTS#_9") (pintype "passive"))
    )
    (net (code "48") (name "Net-(U1-DCD#)") (class "Default")
      (node (ref "JP3") (pin "1") (pinfunction "1_1") (pintype "passive"))
      (node (ref "U1") (pin "12") (pinfunction "DCD#_12") (pintype "passive"))
    )
    (net (code "49") (name "Net-(U1-DSR#)") (class "Default")
      (node (ref "JP3") (pin "3") (pinfunction "3_3") (pintype "passive"))
      (node (ref "U1") (pin "10") (pinfunction "DSR#_10") (pintype "passive"))
    )
    (net (code "50") (name "Net-(U1-DTR#)") (class "Default")
      (node (ref "C2") (pin "2") (pinfunction "2_2") (pintype "passive"))
      (node (ref "U1") (pin "13") (pinfunction "DTR#_13") (pintype "passive"))
    )
    (net (code "51") (name "Net-(U1-RI#)") (class "Default")
      (node (ref "JP3") (pin "2") (pinfunction "2_2") (pintype "passive"))
      (node (ref "U1") (pin "11") (pinfunction "RI#_11") (pintype "passive"))
    )
    (net (code "52") (name "Net-(U1-V3)") (class "Default")
      (node (ref "C1") (pin "2") (pinfunction "2_2") (pintype "passive"))
      (node (ref "U1") (pin "4") (pinfunction "V3_4") (pintype "passive"))
    )
    (net (code "53") (name "Net-(USB1-VBUS)") (class "Default")
      (node (ref "F1") (pin "1") (pinfunction "1_1") (pintype "passive"))
      (node (ref "USB1") (pin "1") (pinfunction "VBUS_1") (pintype "passive"))
    )
    (net (code "54") (name "VIN") (class "Default")
      (node (ref "AMS1") (pin "3") (pinfunction "VIN_3") (pintype "passive"))
      (node (ref "C9") (pin "1") (pinfunction "1_1") (pintype "passive"))
      (node (ref "D1") (pin "2") (pinfunction "K_2") (pintype "passive"))
      (node (ref "JP1") (pin "8") (pinfunction "8_8") (pintype "passive"))
      (node (ref "JP2") (pin "8") (pinfunction "8_8") (pintype "passive"))
      (node (ref "R8") (pin "2") (pinfunction "2_2") (pintype "passive"))
    )
    (net (code "55") (name "unconnected-(JP1-Pad1)") (class "Default")
      (node (ref "JP1") (pin "1") (pinfunction "1_1") (pintype "passive+no_connect"))
    )
    (net (code "56") (name "unconnected-(JP2-Pad1)") (class "Default")
      (node (ref "JP2") (pin "1") (pinfunction "1_1") (pintype "passive+no_connect"))
    )
    (net (code "57") (name "unconnected-(U1-R232-Pad15)") (class "Default")
      (node (ref "U1") (pin "15") (pinfunction "R232_15") (pintype "passive+no_connect"))
    )
    (net (code "58") (name "unconnected-(U1-RTS#-Pad14)") (class "Default")
      (node (ref "U1") (pin "14") (pinfunction "RTS#_14") (pintype "passive+no_connect"))
    )
    (net (code "59") (name "unconnected-(U2-ADC6-Pad19)") (class "Default")
      (node (ref "U2") (pin "19") (pinfunction "ADC6_19") (pintype "input"))
    )
    (net (code "60") (name "unconnected-(U2-ADC7-Pad22)") (class "Default")
      (node (ref "U2") (pin "22") (pinfunction "ADC7_22") (pintype "input"))
    )
    (net (code "61") (name "unconnected-(USB1-ID-Pad4)") (class "Default")
      (node (ref "USB1") (pin "4") (pinfunction "ID_4") (pintype "passive+no_connect"))
    )
  )
)
